# power_supply_stripped_th.net
KiCad netlist of a schematic drawn in EAGLE
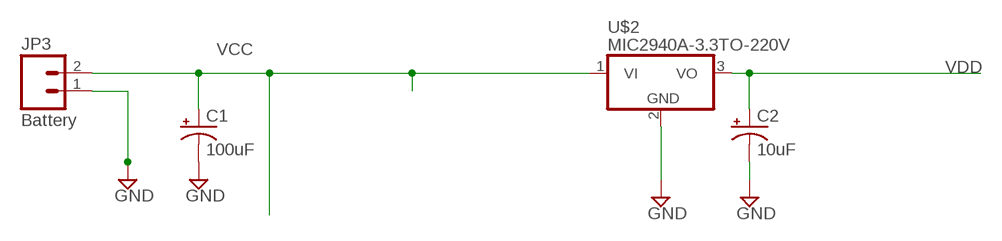
[diagram p0: schematic, sheet 1]

(export (version "E")
  (design (tool "Eeschema 10.0.6"))
  (components
    (comp (ref "C1")
      (value "100uF")
      (footprint "eagle-import:E3,5-8")
      (libsource (lib "eagle-import") (part "CPOL-USE3.5-8"))
    )
    (comp (ref "C2")
      (value "10uF")
      (footprint "eagle-import:E2,5-5")
      (libsource (lib "eagle-import") (part "CPOL-USE2.5-5"))
    )
    (comp (ref "JP3")
      (value "Battery")
      (footprint "eagle-import:1X02")
      (libsource (lib "eagle-import") (part "M02PTH"))
    )
    (comp (ref "U$2")
      (value "MIC2940A-3.3TO-220V")
      (footprint "eagle-import:TO-220V")
      (libsource (lib "eagle-import") (part "MIC2940A-3.3TO-220V"))
    )
  )
  (nets
    (net (code "1") (name "/VCC") (class "Default")
      (node (ref "C1") (pin "+") (pinfunction "+_+") (pintype "passive"))
      (node (ref "JP3") (pin "2") (pinfunction "2_2") (pintype "passive"))
      (node (ref "U$2") (pin "1") (pinfunction "VI_1") (pintype "input"))
    )
    (net (code "2") (name "/VDD") (class "Default")
      (node (ref "C2") (pin "+") (pinfunction "+_+") (pintype "passive"))
      (node (ref "U$2") (pin "3") (pinfunction "VO_3") (pintype "passive"))
    )
    (net (code "3") (name "GND") (class "Default")
      (node (ref "C1") (pin "-") (pinfunction "-_-") (pintype "passive"))
      (node (ref "C2") (pin "-") (pinfunction "-_-") (pintype "passive"))
      (node (ref "JP3") (pin "1") (pinfunction "1_1") (pintype "passive"))
      (node (ref "U$2") (pin "2") (pinfunction "GND_2") (pintype "passive"))
    )
  )
)
